# IR_LED.net
KiCad netlist of a schematic drawn in Altium Designer
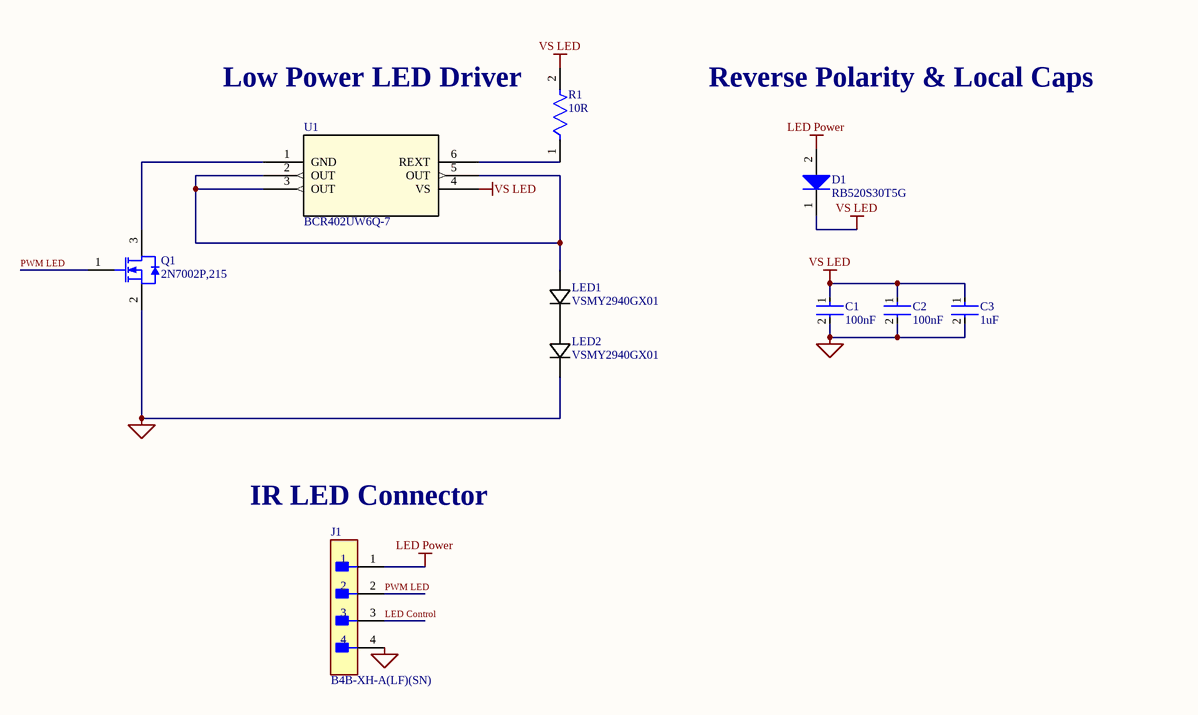
[diagram p0: IR LED.SchDoc]

(export (version "E")
  (design (tool "Eeschema 10.0.6"))
  (components
    (comp (ref "C1")
      (value "100nF")
      (footprint "FP-CL10-IPC_A")
      (description "Cap Ceramic 100nF 25V X7R ±10% Pad SMD 0603 +125°C T/R CL10B104KA8WPNC")
      (fields (field (name "TOLERANCE") "10%"))
      (libsource (lib "Altium Content Vault") (part "b4654b650e69147ec39a6b967a45e02"))
    )
    (comp (ref "C2")
      (value "100nF")
      (footprint "FP-CL10-IPC_A")
      (description "Cap Ceramic 100nF 25V X7R ±10% Pad SMD 0603 +125°C T/R CL10B104KA8WPNC")
      (fields (field (name "TOLERANCE") "10%"))
      (libsource (lib "Altium Content Vault") (part "b4654b650e69147ec39a6b967a45e02"))
    )
    (comp (ref "C3")
      (value "1uF")
      (footprint "FP-GCM21B-0_15-MFG")
      (description "Ceramic Capacitor for Automotive 1uF ±20% 50VDC X7R 0805 Embossed T/R GCM21BR71H105MA03L")
      (libsource (lib "Altium Content Vault") (part "02cd4be3c70576c341d710602a673aa"))
    )
    (comp (ref "D1")
      (value "RB520S30T5G")
      (footprint "ONSC-SOD-523-2-502-01_V")
      (description "Schottky Barrier Diode, 2-Pin SOD-523, Pb-Free, Tape and Reel")
      (fields (field (name "MANUFACTURER") "On Semiconductor"))
      (libsource (lib "Altium Content Vault") (part "ONSC-D-K1A2-2"))
    )
    (comp (ref "J1")
      (value "B4B-XH-A(LF)(SN)")
      (footprint "FP-B4B-XH-A_LF_SN-MFG")
      (description "CONN HEADER VERT 4POS 2.5MM")
      (libsource (lib "Altium Content Vault") (part "299a8cea1bdcbc3624fe62c390fa72c"))
    )
    (comp (ref "LED1")
      (value "VSMY2940GX01")
      (footprint "DIODE_VSMY2940GX01_VIS")
      (description "No Description Available")
      (libsource (lib "VSMY2940GX01") (part "VSMY2940GX01"))
    )
    (comp (ref "LED2")
      (value "VSMY2940GX01")
      (footprint "DIODE_VSMY2940GX01_VIS")
      (description "No Description Available")
      (libsource (lib "VSMY2940GX01") (part "VSMY2940GX01"))
    )
    (comp (ref "Q1")
      (value "2N7002P,215")
      (footprint "NXP-SOT23_L")
      (description "N-Channel Trench MOSFET, 60 V, 0.36 A, -55 to 150 degC, 3-Pin SOT23, Tape and Reel")
      (fields (field (name "MANUFACTURER") "NXP Semiconductors"))
      (libsource (lib "Altium Content Vault") (part "NXP-NMOS-GSD-3_B"))
    )
    (comp (ref "R1")
      (value "10R")
      (footprint "FP-RMCF0805-IPC_B")
      (description "10Ω ±1% 0.125W 0805 Thick Film Chip Resistor AEC-Q200 compliant RMCF0805FG10R0")
      (fields (field (name "TOLERANCE") "1%"))
      (libsource (lib "Altium Content Vault") (part "1029c3af85768c4190bb7ad29bc67b5"))
    )
    (comp (ref "U1")
      (value "BCR402UW6Q-7")
      (footprint "BCR402UW6Q-7_DIO")
      (description "No Description Available")
      (fields (field (name "COPYRIGHT") "Copyright (C) 2026 Ultra Librarian. All rights reserved."))
      (libsource (lib "BCR402UW6Q-7") (part "BCR402UW6Q-7"))
    )
  )
  (nets
    (net (code "1") (name "/LED Control") (class "Default")
      (node (ref "J1") (pin "3") (pinfunction "3_3") (pintype "passive"))
    )
    (net (code "2") (name "/PWM LED") (class "Default")
      (node (ref "J1") (pin "2") (pinfunction "2_2") (pintype "passive"))
      (node (ref "Q1") (pin "1") (pinfunction "G_1") (pintype "passive"))
    )
    (net (code "3") (name "GND") (class "Default")
      (node (ref "C1") (pin "2") (pinfunction "2_2") (pintype "passive"))
      (node (ref "C2") (pin "2") (pinfunction "2_2") (pintype "passive"))
      (node (ref "C3") (pin "2") (pinfunction "2_2") (pintype "passive"))
      (node (ref "J1") (pin "4") (pinfunction "4_4") (pintype "passive"))
      (node (ref "LED2") (pin "1") (pinfunction "1_1") (pintype "passive"))
      (node (ref "Q1") (pin "2") (pinfunction "S_2") (pintype "passive"))
    )
    (net (code "4") (name "LED Power") (class "Default")
      (node (ref "D1") (pin "2") (pinfunction "A_2") (pintype "passive"))
      (node (ref "J1") (pin "1") (pinfunction "1_1") (pintype "passive"))
    )
    (net (code "5") (name "Net-(LED1-Pad1)") (class "Default")
      (node (ref "LED1") (pin "1") (pinfunction "1_1") (pintype "passive"))
      (node (ref "LED2") (pin "2") (pinfunction "2_2") (pintype "passive"))
    )
    (net (code "6") (name "Net-(LED1-Pad2)") (class "Default")
      (node (ref "LED1") (pin "2") (pinfunction "2_2") (pintype "passive"))
      (node (ref "U1") (pin "2") (pinfunction "OUT_2") (pintype "output"))
      (node (ref "U1") (pin "3") (pinfunction "OUT_3") (pintype "output"))
      (node (ref "U1") (pin "5") (pinfunction "OUT_5") (pintype "output"))
    )
    (net (code "7") (name "Net-(Q1-D)") (class "Default")
      (node (ref "Q1") (pin "3") (pinfunction "D_3") (pintype "passive"))
      (node (ref "U1") (pin "1") (pinfunction "GND_1") (pintype "power_in"))
    )
    (net (code "8") (name "Net-(U1-REXT)") (class "Default")
      (node (ref "R1") (pin "1") (pinfunction "1_1") (pintype "passive"))
      (node (ref "U1") (pin "6") (pinfunction "REXT_6") (pintype "passive"))
    )
    (net (code "9") (name "VS LED") (class "Default")
      (node (ref "C1") (pin "1") (pinfunction "1_1") (pintype "passive"))
      (node (ref "C2") (pin "1") (pinfunction "1_1") (pintype "passive"))
      (node (ref "C3") (pin "1") (pinfunction "1_1") (pintype "passive"))
      (node (ref "D1") (pin "1") (pinfunction "K_1") (pintype "passive"))
      (node (ref "R1") (pin "2") (pinfunction "2_2") (pintype "passive"))
      (node (ref "U1") (pin "4") (pinfunction "VS_4") (pintype "power_in"))
    )
  )
)
